# midimixer-channel.net
KiCad netlist of a schematic drawn in EAGLE
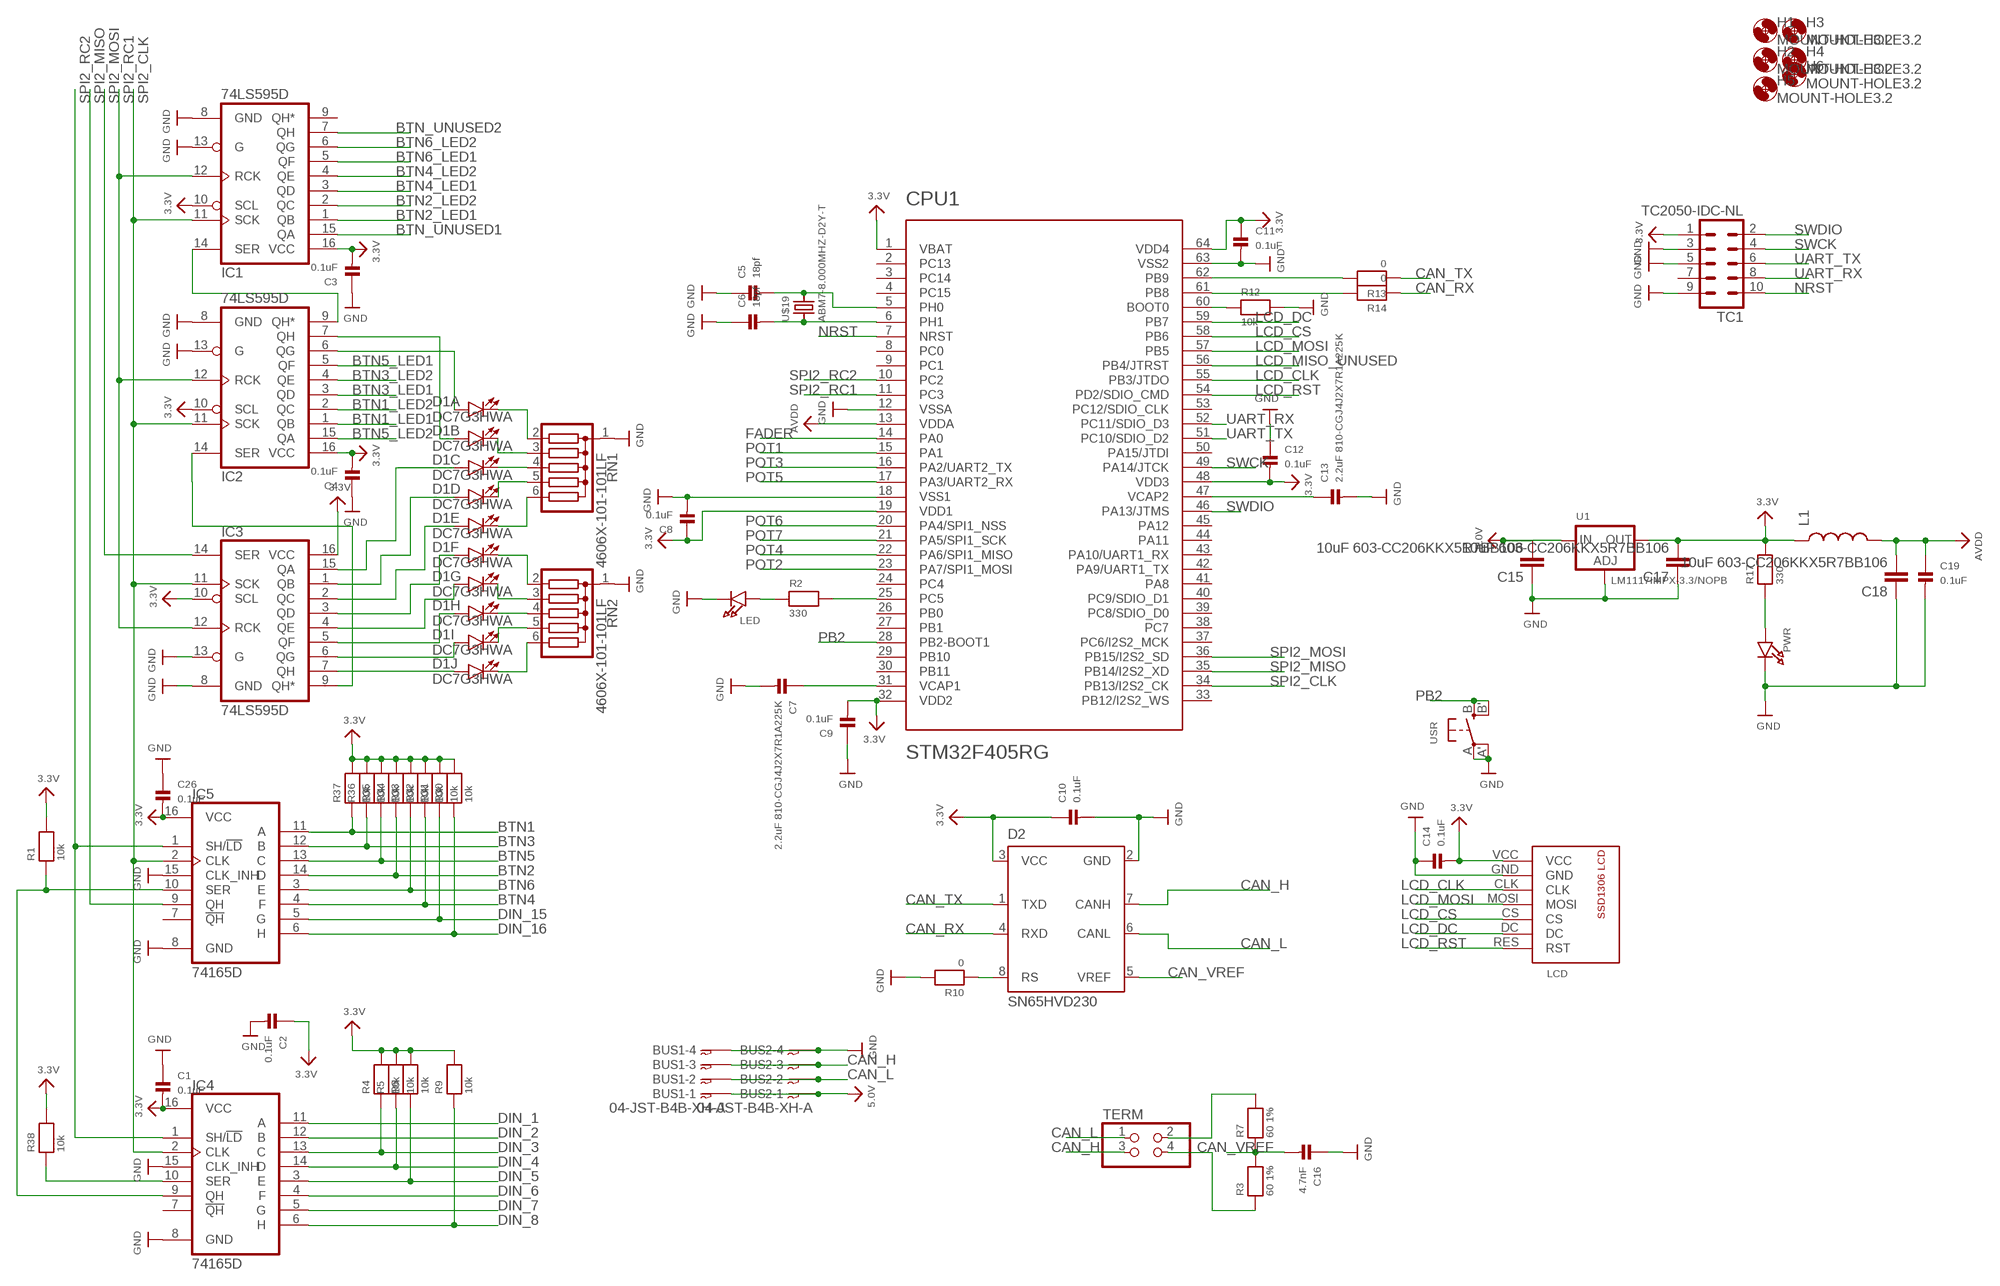
[diagram p0: schematic, sheet 1]
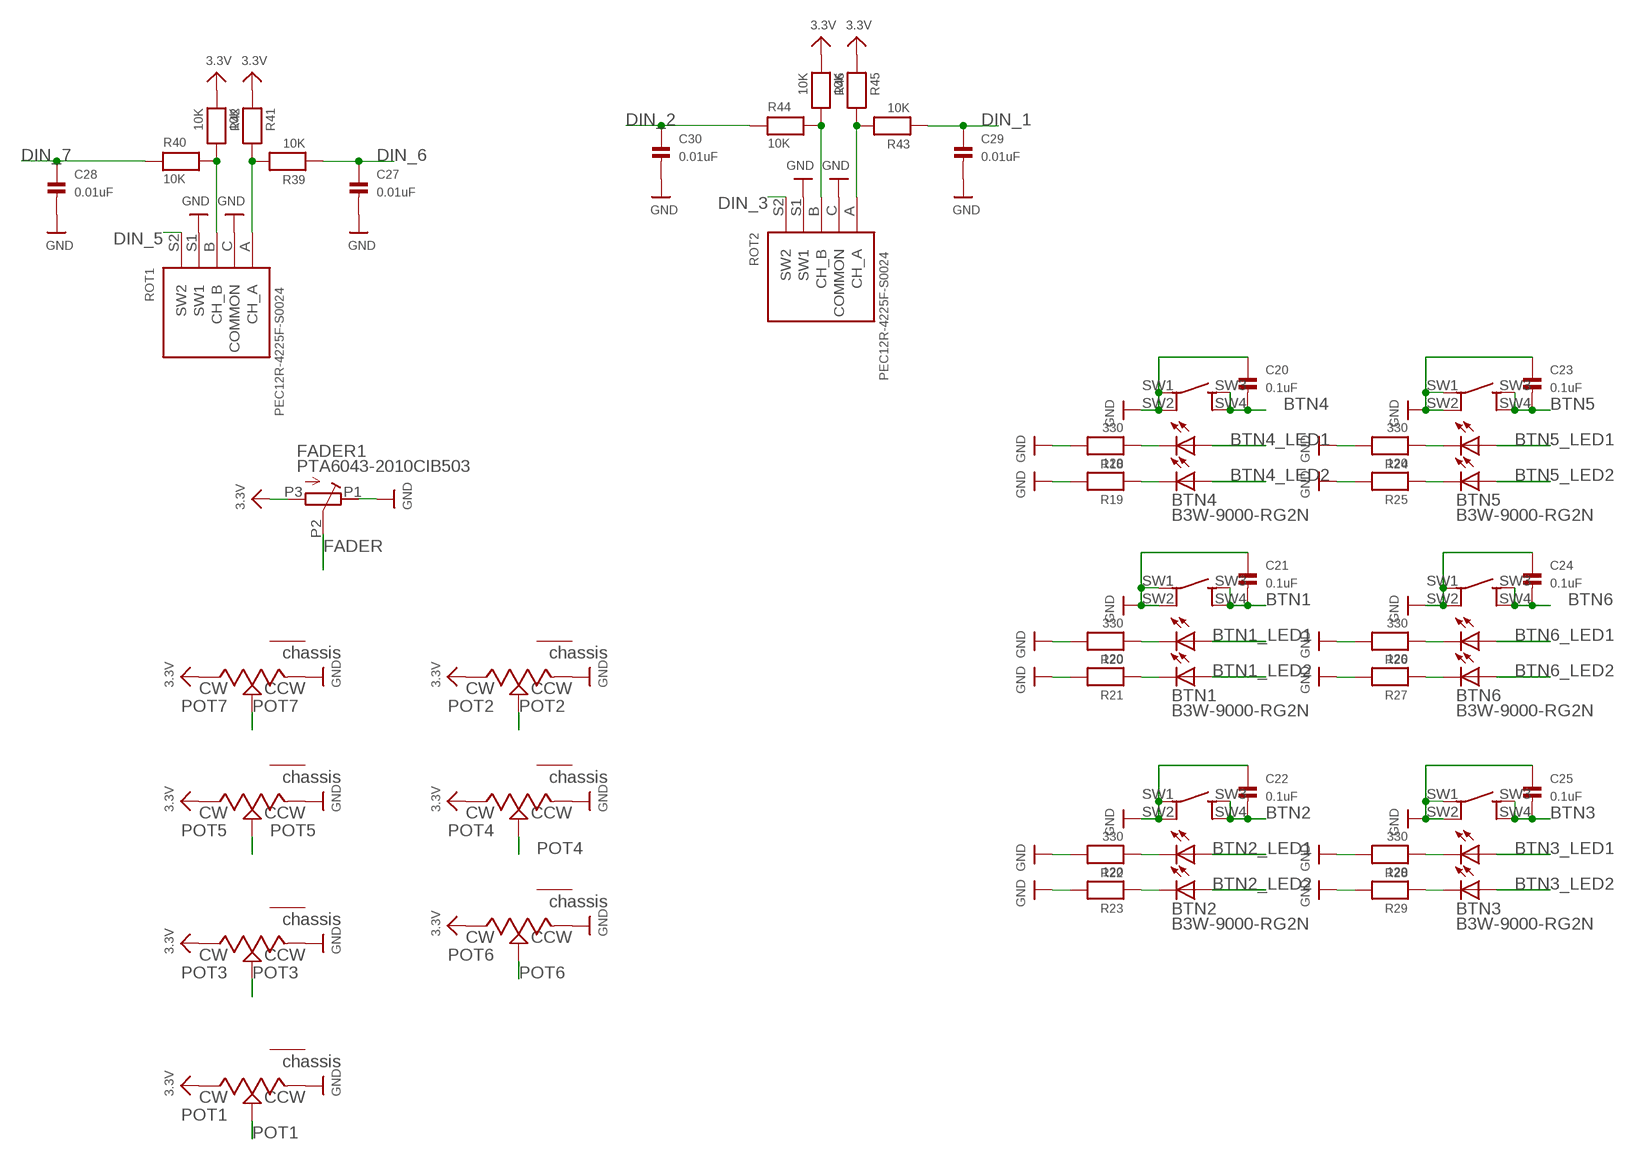
[diagram p1: schematic, sheet 2]

(export (version "E")
  (design (tool "Eeschema 10.0.6"))
  (components
    (comp (ref "BTN1")
      (value "B3W-9000-RG2N")
      (footprint "eagle-import:B3W-9000-X2X")
      (libsource (lib "eagle-import") (part "B3W-9000-RG2N"))
    )
    (comp (ref "BTN2")
      (value "B3W-9000-RG2N")
      (footprint "eagle-import:B3W-9000-X2X")
      (libsource (lib "eagle-import") (part "B3W-9000-RG2N"))
    )
    (comp (ref "BTN3")
      (value "B3W-9000-RG2N")
      (footprint "eagle-import:B3W-9000-X2X")
      (libsource (lib "eagle-import") (part "B3W-9000-RG2N"))
    )
    (comp (ref "BTN4")
      (value "B3W-9000-RG2N")
      (footprint "eagle-import:B3W-9000-X2X")
      (libsource (lib "eagle-import") (part "B3W-9000-RG2N"))
    )
    (comp (ref "BTN5")
      (value "B3W-9000-RG2N")
      (footprint "eagle-import:B3W-9000-X2X")
      (libsource (lib "eagle-import") (part "B3W-9000-RG2N"))
    )
    (comp (ref "BTN6")
      (value "B3W-9000-RG2N")
      (footprint "eagle-import:B3W-9000-X2X")
      (libsource (lib "eagle-import") (part "B3W-9000-RG2N"))
    )
    (comp (ref "C20")
      (value "0.1uF")
      (footprint "eagle-import:0603")
      (libsource (lib "eagle-import") (part "CAP_CERAMIC0603"))
    )
    (comp (ref "C21")
      (value "0.1uF")
      (footprint "eagle-import:0603")
      (libsource (lib "eagle-import") (part "CAP_CERAMIC0603"))
    )
    (comp (ref "C22")
      (value "0.1uF")
      (footprint "eagle-import:0603")
      (libsource (lib "eagle-import") (part "CAP_CERAMIC0603"))
    )
    (comp (ref "C23")
      (value "0.1uF")
      (footprint "eagle-import:0603")
      (libsource (lib "eagle-import") (part "CAP_CERAMIC0603"))
    )
    (comp (ref "C24")
      (value "0.1uF")
      (footprint "eagle-import:0603")
      (libsource (lib "eagle-import") (part "CAP_CERAMIC0603"))
    )
    (comp (ref "C25")
      (value "0.1uF")
      (footprint "eagle-import:0603")
      (libsource (lib "eagle-import") (part "CAP_CERAMIC0603"))
    )
    (comp (ref "C27")
      (value "0.01uF")
      (footprint "eagle-import:0603")
      (libsource (lib "eagle-import") (part "CAP_CERAMIC0603"))
    )
    (comp (ref "C28")
      (value "0.01uF")
      (footprint "eagle-import:0603")
      (libsource (lib "eagle-import") (part "CAP_CERAMIC0603"))
    )
    (comp (ref "C29")
      (value "0.01uF")
      (footprint "eagle-import:0603")
      (libsource (lib "eagle-import") (part "CAP_CERAMIC0603"))
    )
    (comp (ref "C30")
      (value "0.01uF")
      (footprint "eagle-import:0603")
      (libsource (lib "eagle-import") (part "CAP_CERAMIC0603"))
    )
    (comp (ref "FADER1")
      (value "PTA6043-2010CIB503")
      (footprint "eagle-import:PTA6043-2015CPB103")
      (libsource (lib "eagle-import") (part "PTA6043-2015CPB103"))
    )
    (comp (ref "POT1")
      (value "POTENTIOMETERPTV09A_VERTICAL")
      (footprint "eagle-import:PTV09A-4")
      (libsource (lib "eagle-import") (part "POTENTIOMETERPTV09A_VERTICAL"))
    )
    (comp (ref "POT2")
      (value "POTENTIOMETERPTV09A_VERTICAL")
      (footprint "eagle-import:PTV09A-4")
      (libsource (lib "eagle-import") (part "POTENTIOMETERPTV09A_VERTICAL"))
    )
    (comp (ref "POT3")
      (value "POTENTIOMETERPTV09A_VERTICAL")
      (footprint "eagle-import:PTV09A-4")
      (libsource (lib "eagle-import") (part "POTENTIOMETERPTV09A_VERTICAL"))
    )
    (comp (ref "POT4")
      (value "POTENTIOMETERPTV09A_VERTICAL")
      (footprint "eagle-import:PTV09A-4")
      (libsource (lib "eagle-import") (part "POTENTIOMETERPTV09A_VERTICAL"))
    )
    (comp (ref "POT5")
      (value "POTENTIOMETERPTV09A_VERTICAL")
      (footprint "eagle-import:PTV09A-4")
      (libsource (lib "eagle-import") (part "POTENTIOMETERPTV09A_VERTICAL"))
    )
    (comp (ref "POT6")
      (value "POTENTIOMETERPTV09A_VERTICAL")
      (footprint "eagle-import:PTV09A-4")
      (libsource (lib "eagle-import") (part "POTENTIOMETERPTV09A_VERTICAL"))
    )
    (comp (ref "POT7")
      (value "POTENTIOMETERPTV09A_VERTICAL")
      (footprint "eagle-import:PTV09A-4")
      (libsource (lib "eagle-import") (part "POTENTIOMETERPTV09A_VERTICAL"))
    )
    (comp (ref "R18")
      (value "330")
      (footprint "eagle-import:0603")
      (libsource (lib "eagle-import") (part "RESISTOR0603"))
    )
    (comp (ref "R19")
      (value "120")
      (footprint "eagle-import:0603")
      (libsource (lib "eagle-import") (part "RESISTOR0603"))
    )
    (comp (ref "R20")
      (value "330")
      (footprint "eagle-import:0603")
      (libsource (lib "eagle-import") (part "RESISTOR0603"))
    )
    (comp (ref "R21")
      (value "120")
      (footprint "eagle-import:0603")
      (libsource (lib "eagle-import") (part "RESISTOR0603"))
    )
    (comp (ref "R22")
      (value "330")
      (footprint "eagle-import:0603")
      (libsource (lib "eagle-import") (part "RESISTOR0603"))
    )
    (comp (ref "R23")
      (value "120")
      (footprint "eagle-import:0603")
      (libsource (lib "eagle-import") (part "RESISTOR0603"))
    )
    (comp (ref "R24")
      (value "330")
      (footprint "eagle-import:0603")
      (libsource (lib "eagle-import") (part "RESISTOR0603"))
    )
    (comp (ref "R25")
      (value "120")
      (footprint "eagle-import:0603")
      (libsource (lib "eagle-import") (part "RESISTOR0603"))
    )
    (comp (ref "R26")
      (value "330")
      (footprint "eagle-import:0603")
      (libsource (lib "eagle-import") (part "RESISTOR0603"))
    )
    (comp (ref "R27")
      (value "120")
      (footprint "eagle-import:0603")
      (libsource (lib "eagle-import") (part "RESISTOR0603"))
    )
    (comp (ref "R28")
      (value "330")
      (footprint "eagle-import:0603")
      (libsource (lib "eagle-import") (part "RESISTOR0603"))
    )
    (comp (ref "R29")
      (value "120")
      (footprint "eagle-import:0603")
      (libsource (lib "eagle-import") (part "RESISTOR0603"))
    )
    (comp (ref "R39")
      (value "10K")
      (footprint "eagle-import:0603")
      (libsource (lib "eagle-import") (part "RESISTOR0603"))
    )
    (comp (ref "R40")
      (value "10K")
      (footprint "eagle-import:0603")
      (libsource (lib "eagle-import") (part "RESISTOR0603"))
    )
    (comp (ref "R41")
      (value "10K")
      (footprint "eagle-import:0603")
      (libsource (lib "eagle-import") (part "RESISTOR0603"))
    )
    (comp (ref "R42")
      (value "10K")
      (footprint "eagle-import:0603")
      (libsource (lib "eagle-import") (part "RESISTOR0603"))
    )
    (comp (ref "R43")
      (value "10K")
      (footprint "eagle-import:0603")
      (libsource (lib "eagle-import") (part "RESISTOR0603"))
    )
    (comp (ref "R44")
      (value "10K")
      (footprint "eagle-import:0603")
      (libsource (lib "eagle-import") (part "RESISTOR0603"))
    )
    (comp (ref "R45")
      (value "10K")
      (footprint "eagle-import:0603")
      (libsource (lib "eagle-import") (part "RESISTOR0603"))
    )
    (comp (ref "R46")
      (value "10K")
      (footprint "eagle-import:0603")
      (libsource (lib "eagle-import") (part "RESISTOR0603"))
    )
    (comp (ref "ROT1")
      (value "PEC12R-4225F-S0024")
      (footprint "eagle-import:PEC111-4XXXK-SXXXX")
      (libsource (lib "eagle-import") (part "PEC11-4215K-S0024"))
    )
    (comp (ref "ROT2")
      (value "PEC12R-4225F-S0024")
      (footprint "eagle-import:PEC111-4XXXK-SXXXX")
      (libsource (lib "eagle-import") (part "PEC11-4215K-S0024"))
    )
    (comp (ref "BUS1")
      (value "04-JST-B4B-XH-A")
      (footprint "eagle-import:B4B-XH")
      (libsource (lib "eagle-import") (part "04-JST-B4B-XH-A"))
    )
    (comp (ref "BUS2")
      (value "04-JST-B4B-XH-A")
      (footprint "eagle-import:B4B-XH")
      (libsource (lib "eagle-import") (part "04-JST-B4B-XH-A"))
    )
    (comp (ref "C1")
      (value "0.1uF")
      (footprint "eagle-import:0603")
      (libsource (lib "eagle-import") (part "CAP_CERAMIC0603"))
    )
    (comp (ref "C2")
      (value "0.1uF")
      (footprint "eagle-import:0603")
      (libsource (lib "eagle-import") (part "CAP_CERAMIC0603"))
    )
    (comp (ref "C3")
      (value "0.1uF")
      (footprint "eagle-import:0603")
      (libsource (lib "eagle-import") (part "CAP_CERAMIC0603"))
    )
    (comp (ref "C4")
      (value "0.1uF")
      (footprint "eagle-import:0603")
      (libsource (lib "eagle-import") (part "CAP_CERAMIC0603"))
    )
    (comp (ref "C5")
      (value "18pf")
      (footprint "eagle-import:0603")
      (libsource (lib "eagle-import") (part "CAP_CERAMIC0603"))
    )
    (comp (ref "C6")
      (value "18pf")
      (footprint "eagle-import:0603")
      (libsource (lib "eagle-import") (part "CAP_CERAMIC0603"))
    )
    (comp (ref "C7")
      (value "2.2uF 810-CGJ4J2X7R1A225K")
      (footprint "eagle-import:0805")
      (libsource (lib "eagle-import") (part "CAP_CERAMIC0805"))
    )
    (comp (ref "C8")
      (value "0.1uF")
      (footprint "eagle-import:0603")
      (libsource (lib "eagle-import") (part "CAP_CERAMIC0603"))
    )
    (comp (ref "C9")
      (value "0.1uF")
      (footprint "eagle-import:0603")
      (libsource (lib "eagle-import") (part "CAP_CERAMIC0603"))
    )
    (comp (ref "C10")
      (value "0.1uF")
      (footprint "eagle-import:0603")
      (libsource (lib "eagle-import") (part "CAP_CERAMIC0603"))
    )
    (comp (ref "C11")
      (value "0.1uF")
      (footprint "eagle-import:0603")
      (libsource (lib "eagle-import") (part "CAP_CERAMIC0603"))
    )
    (comp (ref "C12")
      (value "0.1uF")
      (footprint "eagle-import:0603")
      (libsource (lib "eagle-import") (part "CAP_CERAMIC0603"))
    )
    (comp (ref "C13")
      (value "2.2uF 810-CGJ4J2X7R1A225K")
      (footprint "eagle-import:0805")
      (libsource (lib "eagle-import") (part "CAP_CERAMIC0805"))
    )
    (comp (ref "C14")
      (value "0.1uF")
      (footprint "eagle-import:0603")
      (libsource (lib "eagle-import") (part "CAP_CERAMIC0603"))
    )
    (comp (ref "C15")
      (value "10uF 603-CC206KKX5R7BB106")
      (footprint "eagle-import:1206")
      (libsource (lib "eagle-import") (part "CAP1206"))
    )
    (comp (ref "C16")
      (value "4.7nF")
      (footprint "eagle-import:0603")
      (libsource (lib "eagle-import") (part "CAP_CERAMIC0603"))
    )
    (comp (ref "C17")
      (value "10uF 603-CC206KKX5R7BB106")
      (footprint "eagle-import:1206")
      (libsource (lib "eagle-import") (part "CAP1206"))
    )
    (comp (ref "C18")
      (value "10uF 603-CC206KKX5R7BB106")
      (footprint "eagle-import:1206")
      (libsource (lib "eagle-import") (part "CAP1206"))
    )
    (comp (ref "C19")
      (value "0.1uF")
      (footprint "eagle-import:0603")
      (libsource (lib "eagle-import") (part "CAP_CERAMIC0603"))
    )
    (comp (ref "C26")
      (value "0.1uF")
      (footprint "eagle-import:0603")
      (libsource (lib "eagle-import") (part "CAP_CERAMIC0603"))
    )
    (comp (ref "CPU1")
      (value "STM32F405RG")
      (footprint "eagle-import:TQFP64")
      (libsource (lib "eagle-import") (part "STM32F405RG"))
    )
    (comp (ref "D1")
      (value "DC7G3HWA")
      (footprint "eagle-import:LED_BARGAPH_10")
      (libsource (lib "eagle-import") (part "LED_BARGRAPH_10"))
    )
    (comp (ref "D2")
      (value "SN65HVD230")
      (footprint "eagle-import:SO8")
      (libsource (lib "eagle-import") (part "SN65HVD230"))
    )
    (comp (ref "H1")
      (value "MOUNT-HOLE3.2")
      (footprint "eagle-import:3,2")
      (libsource (lib "eagle-import") (part "MOUNT-HOLE3.2"))
    )
    (comp (ref "H2")
      (value "MOUNT-HOLE3.2")
      (footprint "eagle-import:3,2")
      (libsource (lib "eagle-import") (part "MOUNT-HOLE3.2"))
    )
    (comp (ref "H3")
      (value "MOUNT-HOLE3.2")
      (footprint "eagle-import:3,2")
      (libsource (lib "eagle-import") (part "MOUNT-HOLE3.2"))
    )
    (comp (ref "H4")
      (value "MOUNT-HOLE3.2")
      (footprint "eagle-import:3,2")
      (libsource (lib "eagle-import") (part "MOUNT-HOLE3.2"))
    )
    (comp (ref "H5")
      (value "MOUNT-HOLE3.2")
      (footprint "eagle-import:3,2")
      (libsource (lib "eagle-import") (part "MOUNT-HOLE3.2"))
    )
    (comp (ref "H6")
      (value "MOUNT-HOLE3.2")
      (footprint "eagle-import:3,2")
      (libsource (lib "eagle-import") (part "MOUNT-HOLE3.2"))
    )
    (comp (ref "IC1")
      (value "74LS595D")
      (footprint "eagle-import:SO16")
      (libsource (lib "eagle-import") (part "74595DLS"))
    )
    (comp (ref "IC2")
      (value "74LS595D")
      (footprint "eagle-import:SO16")
      (libsource (lib "eagle-import") (part "74595DLS"))
    )
    (comp (ref "IC3")
      (value "74LS595D")
      (footprint "eagle-import:SO16")
      (libsource (lib "eagle-import") (part "74595DLS"))
    )
    (comp (ref "IC4")
      (value "74165D")
      (footprint "eagle-import:SO16")
      (libsource (lib "eagle-import") (part "74165D"))
    )
    (comp (ref "IC5")
      (value "74165D")
      (footprint "eagle-import:SO16")
      (libsource (lib "eagle-import") (part "74165D"))
    )
    (comp (ref "L1")
      (value "INDUCTOR0805")
      (footprint "eagle-import:0805")
      (libsource (lib "eagle-import") (part "INDUCTOR0805"))
    )
    (comp (ref "LCD")
      (value "SSD1306-7PINWITHOUT-HOLES")
      (footprint "eagle-import:SSD1306-7PIN-NO-HOLES")
      (libsource (lib "eagle-import") (part "SSD1306-7PINWITHOUT-HOLES"))
    )
    (comp (ref "LED")
      (value "LED0603")
      (footprint "eagle-import:CHIPLED_0603")
      (libsource (lib "eagle-import") (part "LED0603"))
    )
    (comp (ref "PWR")
      (value "LED0603")
      (footprint "eagle-import:CHIPLED_0603")
      (libsource (lib "eagle-import") (part "LED0603"))
    )
    (comp (ref "R1")
      (value "10k")
      (footprint "eagle-import:_0603")
      (libsource (lib "eagle-import") (part "RESISTOR_0603"))
    )
    (comp (ref "R2")
      (value "330")
      (footprint "eagle-import:0603")
      (libsource (lib "eagle-import") (part "RESISTOR0603"))
    )
    (comp (ref "R3")
      (value "60 1%")
      (footprint "eagle-import:0603")
      (libsource (lib "eagle-import") (part "RESISTOR0603"))
    )
    (comp (ref "R4")
      (value "10k")
      (footprint "eagle-import:_0603")
      (libsource (lib "eagle-import") (part "RESISTOR_0603"))
    )
    (comp (ref "R5")
      (value "10k")
      (footprint "eagle-import:_0603")
      (libsource (lib "eagle-import") (part "RESISTOR_0603"))
    )
    (comp (ref "R6")
      (value "10k")
      (footprint "eagle-import:_0603")
      (libsource (lib "eagle-import") (part "RESISTOR_0603"))
    )
    (comp (ref "R7")
      (value "60 1%")
      (footprint "eagle-import:0603")
      (libsource (lib "eagle-import") (part "RESISTOR0603"))
    )
    (comp (ref "R9")
      (value "10k")
      (footprint "eagle-import:_0603")
      (libsource (lib "eagle-import") (part "RESISTOR_0603"))
    )
    (comp (ref "R10")
      (value "0")
      (footprint "eagle-import:_0603")
      (libsource (lib "eagle-import") (part "RESISTOR_0603"))
    )
    (comp (ref "R12")
      (value "10k")
      (footprint "eagle-import:_0603")
      (libsource (lib "eagle-import") (part "RESISTOR_0603"))
    )
    (comp (ref "R13")
      (value "0")
      (footprint "eagle-import:_0603")
      (libsource (lib "eagle-import") (part "RESISTOR_0603"))
    )
    (comp (ref "R14")
      (value "0")
      (footprint "eagle-import:_0603")
      (libsource (lib "eagle-import") (part "RESISTOR_0603"))
    )
    (comp (ref "R17")
      (value "330")
      (footprint "eagle-import:0603")
      (libsource (lib "eagle-import") (part "RESISTOR0603"))
    )
    (comp (ref "R30")
      (value "10k")
      (footprint "eagle-import:_0603")
      (libsource (lib "eagle-import") (part "RESISTOR_0603"))
    )
    (comp (ref "R31")
      (value "10k")
      (footprint "eagle-import:_0603")
      (libsource (lib "eagle-import") (part "RESISTOR_0603"))
    )
    (comp (ref "R32")
      (value "10k")
      (footprint "eagle-import:_0603")
      (libsource (lib "eagle-import") (part "RESISTOR_0603"))
    )
    (comp (ref "R33")
      (value "10k")
      (footprint "eagle-import:_0603")
      (libsource (lib "eagle-import") (part "RESISTOR_0603"))
    )
    (comp (ref "R34")
      (value "10k")
      (footprint "eagle-import:_0603")
      (libsource (lib "eagle-import") (part "RESISTOR_0603"))
    )
    (comp (ref "R35")
      (value "10k")
      (footprint "eagle-import:_0603")
      (libsource (lib "eagle-import") (part "RESISTOR_0603"))
    )
    (comp (ref "R36")
      (value "10k")
      (footprint "eagle-import:_0603")
      (libsource (lib "eagle-import") (part "RESISTOR_0603"))
    )
    (comp (ref "R37")
      (value "10k")
      (footprint "eagle-import:_0603")
      (libsource (lib "eagle-import") (part "RESISTOR_0603"))
    )
    (comp (ref "R38")
      (value "10k")
      (footprint "eagle-import:_0603")
      (libsource (lib "eagle-import") (part "RESISTOR_0603"))
    )
    (comp (ref "RN1")
      (value "4606X-101-101LF")
      (footprint "eagle-import:SIL6")
      (libsource (lib "eagle-import") (part "G05R"))
    )
    (comp (ref "RN2")
      (value "4606X-101-101LF")
      (footprint "eagle-import:SIL6")
      (libsource (lib "eagle-import") (part "G05R"))
    )
    (comp (ref "TC1")
      (value "TC2050-IDC-NL")
      (footprint "eagle-import:TC2050-IDC-NL")
      (libsource (lib "eagle-import") (part "TC2050-IDC-NL"))
    )
    (comp (ref "TERM")
      (value "PINHD-2X2")
      (footprint "eagle-import:2X02")
      (libsource (lib "eagle-import") (part "PINHD-2X2"))
    )
    (comp (ref "U$19")
      (value "ABM7-8.000MHZ-D2Y-T")
      (footprint "eagle-import:ABM7-8.000MHZ-D2Y-T")
      (libsource (lib "eagle-import") (part "ABM7-8.000MHZ-D2Y-T"))
    )
    (comp (ref "U1")
      (value "LM1117IMPX-3.3/NOPB")
      (footprint "eagle-import:SOT223-R")
      (libsource (lib "eagle-import") (part "LM1117SOT223-REFLOW"))
    )
    (comp (ref "USR")
      (value "SWITCH_TACT_SMT")
      (footprint "eagle-import:EVQ-Q2")
      (libsource (lib "eagle-import") (part "SWITCH_TACT_SMT"))
    )
  )
  (nets
    (net (code "1") (name "3.3V") (class "Default")
      (node (ref "C1") (pin "2") (pinfunction "P$2_2") (pintype "passive"))
      (node (ref "C10") (pin "1") (pinfunction "P$1_1") (pintype "passive"))
      (node (ref "C11") (pin "1") (pinfunction "P$1_1") (pintype "passive"))
      (node (ref "C12") (pin "2") (pinfunction "P$2_2") (pintype "passive"))
      (node (ref "C14") (pin "2") (pinfunction "P$2_2") (pintype "passive"))
      (node (ref "C17") (pin "2") (pinfunction "2_2") (pintype "passive"))
      (node (ref "C2") (pin "1") (pinfunction "P$1_1") (pintype "passive"))
      (node (ref "C26") (pin "2") (pinfunction "P$2_2") (pintype "passive"))
      (node (ref "C3") (pin "2") (pinfunction "P$2_2") (pintype "passive"))
      (node (ref "C4") (pin "2") (pinfunction "P$2_2") (pintype "passive"))
      (node (ref "C8") (pin "1") (pinfunction "P$1_1") (pintype "passive"))
      (node (ref "C9") (pin "2") (pinfunction "P$2_2") (pintype "passive"))
      (node (ref "CPU1") (pin "1") (pinfunction "VBAT_1") (pintype "bidirectional"))
      (node (ref "CPU1") (pin "19") (pinfunction "VDD1_19") (pintype "bidirectional"))
      (node (ref "CPU1") (pin "32") (pinfunction "VDD2_32") (pintype "bidirectional"))
      (node (ref "CPU1") (pin "48") (pinfunction "VDD3_48") (pintype "bidirectional"))
      (node (ref "CPU1") (pin "64") (pinfunction "VDD4_64") (pintype "bidirectional"))
      (node (ref "D2") (pin "3") (pinfunction "VCC_3") (pintype "power_in"))
      (node (ref "FADER1") (pin "P3") (pinfunction "E_P3") (pintype "passive"))
      (node (ref "IC1") (pin "10") (pinfunction "SCL_10") (pintype "input"))
      (node (ref "IC1") (pin "16") (pinfunction "VCC_16") (pintype "power_in"))
      (node (ref "IC2") (pin "10") (pinfunction "SCL_10") (pintype "input"))
      (node (ref "IC2") (pin "16") (pinfunction "VCC_16") (pintype "power_in"))
      (node (ref "IC3") (pin "10") (pinfunction "SCL_10") (pintype "input"))
      (node (ref "IC3") (pin "16") (pinfunction "VCC_16") (pintype "power_in"))
      (node (ref "IC4") (pin "16") (pinfunction "VCC_16") (pintype "power_in"))
      (node (ref "IC5") (pin "16") (pinfunction "VCC_16") (pintype "power_in"))
      (node (ref "L1") (pin "1") (pinfunction "1_1") (pintype "passive"))
      (node (ref "LCD") (pin "VCC") (pinfunction "VCC_VCC") (pintype "bidirectional"))
      (node (ref "POT1") (pin "CW") (pinfunction "CW_CW") (pintype "passive"))
      (node (ref "POT2") (pin "CW") (pinfunction "CW_CW") (pintype "passive"))
      (node (ref "POT3") (pin "CW") (pinfunction "CW_CW") (pintype "passive"))
      (node (ref "POT4") (pin "CW") (pinfunction "CW_CW") (pintype "passive"))
      (node (ref "POT5") (pin "CW") (pinfunction "CW_CW") (pintype "passive"))
      (node (ref "POT6") (pin "CW") (pinfunction "CW_CW") (pintype "passive"))
      (node (ref "POT7") (pin "CW") (pinfunction "CW_CW") (pintype "passive"))
      (node (ref "R1") (pin "2") (pinfunction "2_2") (pintype "passive"))
      (node (ref "R17") (pin "2") (pinfunction "2_2") (pintype "passive"))
      (node (ref "R30") (pin "2") (pinfunction "2_2") (pintype "passive"))
      (node (ref "R31") (pin "2") (pinfunction "2_2") (pintype "passive"))
      (node (ref "R32") (pin "2") (pinfunction "2_2") (pintype "passive"))
      (node (ref "R33") (pin "2") (pinfunction "2_2") (pintype "passive"))
      (node (ref "R34") (pin "2") (pinfunction "2_2") (pintype "passive"))
      (node (ref "R35") (pin "2") (pinfunction "2_2") (pintype "passive"))
      (node (ref "R36") (pin "2") (pinfunction "2_2") (pintype "passive"))
      (node (ref "R37") (pin "2") (pinfunction "2_2") (pintype "passive"))
      (node (ref "R38") (pin "2") (pinfunction "2_2") (pintype "passive"))
      (node (ref "R4") (pin "2") (pinfunction "2_2") (pintype "passive"))
      (node (ref "R41") (pin "1") (pinfunction "1_1") (pintype "passive"))
      (node (ref "R42") (pin "1") (pinfunction "1_1") (pintype "passive"))
      (node (ref "R45") (pin "1") (pinfunction "1_1") (pintype "passive"))
      (node (ref "R46") (pin "1") (pinfunction "1_1") (pintype "passive"))
      (node (ref "R5") (pin "2") (pinfunction "2_2") (pintype "passive"))
      (node (ref "R6") (pin "2") (pinfunction "2_2") (pintype "passive"))
      (node (ref "R9") (pin "2") (pinfunction "2_2") (pintype "passive"))
      (node (ref "TC1") (pin "1") (pinfunction "1_1") (pintype "passive"))
      (node (ref "U1") (pin "2") (pinfunction "OUT_2") (pintype "passive"))
    )
    (net (code "2") (name "5.0V") (class "Default")
      (node (ref "BUS1") (pin "P$1") (pinfunction "1_P$1") (pintype "passive"))
      (node (ref "BUS2") (pin "P$1") (pinfunction "1_P$1") (pintype "passive"))
      (node (ref "C15") (pin "2") (pinfunction "2_2") (pintype "passive"))
      (node (ref "U1") (pin "3") (pinfunction "IN_3") (pintype "input"))
    )
    (net (code "3") (name "AVDD") (class "Default")
      (node (ref "C18") (pin "2") (pinfunction "2_2") (pintype "passive"))
      (node (ref "C19") (pin "1") (pinfunction "P$1_1") (pintype "passive"))
      (node (ref "CPU1") (pin "13") (pinfunction "VDDA_13") (pintype "bidirectional"))
      (node (ref "L1") (pin "2") (pinfunction "2_2") (pintype "passive"))
    )
    (net (code "4") (name "BTN1") (class "Default")
      (node (ref "BTN1") (pin "SW3") (pinfunction "SW2_A_SW3") (pintype "passive"))
      (node (ref "BTN1") (pin "SW4") (pinfunction "SW2_B_SW4") (pintype "passive"))
      (node (ref "C21") (pin "2") (pinfunction "P$2_2") (pintype "passive"))
      (node (ref "IC5") (pin "11") (pinfunction "A_11") (pintype "tri_state"))
      (node (ref "R37") (pin "1") (pinfunction "1_1") (pintype "passive"))
    )
    (net (code "5") (name "BTN1_LED1") (class "Default")
      (node (ref "BTN1") (pin "LED1+") (pinfunction "LED1+_LED1+") (pintype "passive"))
      (node (ref "IC2") (pin "1") (pinfunction "QB_1") (pintype "tri_state"))
    )
    (net (code "6") (name "BTN1_LED2") (class "Default")
      (node (ref "BTN1") (pin "LED2+") (pinfunction "LED2+_LED2+") (pintype "passive"))
      (node (ref "IC2") (pin "2") (pinfunction "QC_2") (pintype "tri_state"))
    )
    (net (code "7") (name "BTN2") (class "Default")
      (node (ref "BTN2") (pin "SW3") (pinfunction "SW2_A_SW3") (pintype "passive"))
      (node (ref "BTN2") (pin "SW4") (pinfunction "SW2_B_SW4") (pintype "passive"))
      (node (ref "C22") (pin "2") (pinfunction "P$2_2") (pintype "passive"))
      (node (ref "IC5") (pin "14") (pinfunction "D_14") (pintype "tri_state"))
      (node (ref "R34") (pin "1") (pinfunction "1_1") (pintype "passive"))
    )
    (net (code "8") (name "BTN2_LED1") (class "Default")
      (node (ref "BTN2") (pin "LED1+") (pinfunction "LED1+_LED1+") (pintype "passive"))
      (node (ref "IC1") (pin "1") (pinfunction "QB_1") (pintype "tri_state"))
    )
    (net (code "9") (name "BTN2_LED2") (class "Default")
      (node (ref "BTN2") (pin "LED2+") (pinfunction "LED2+_LED2+") (pintype "passive"))
      (node (ref "IC1") (pin "2") (pinfunction "QC_2") (pintype "tri_state"))
    )
    (net (code "10") (name "BTN3") (class "Default")
      (node (ref "BTN3") (pin "SW3") (pinfunction "SW2_A_SW3") (pintype "passive"))
      (node (ref "BTN3") (pin "SW4") (pinfunction "SW2_B_SW4") (pintype "passive"))
      (node (ref "C25") (pin "2") (pinfunction "P$2_2") (pintype "passive"))
      (node (ref "IC5") (pin "12") (pinfunction "B_12") (pintype "tri_state"))
      (node (ref "R36") (pin "1") (pinfunction "1_1") (pintype "passive"))
    )
    (net (code "11") (name "BTN3_LED1") (class "Default")
      (node (ref "BTN3") (pin "LED1+") (pinfunction "LED1+_LED1+") (pintype "passive"))
      (node (ref "IC2") (pin "3") (pinfunction "QD_3") (pintype "tri_state"))
    )
    (net (code "12") (name "BTN3_LED2") (class "Default")
      (node (ref "BTN3") (pin "LED2+") (pinfunction "LED2+_LED2+") (pintype "passive"))
      (node (ref "IC2") (pin "4") (pinfunction "QE_4") (pintype "tri_state"))
    )
    (net (code "13") (name "BTN4") (class "Default")
      (node (ref "BTN4") (pin "SW3") (pinfunction "SW2_A_SW3") (pintype "passive"))
      (node (ref "BTN4") (pin "SW4") (pinfunction "SW2_B_SW4") (pintype "passive"))
      (node (ref "C20") (pin "2") (pinfunction "P$2_2") (pintype "passive"))
      (node (ref "IC5") (pin "4") (pinfunction "F_4") (pintype "tri_state"))
      (node (ref "R32") (pin "1") (pinfunction "1_1") (pintype "passive"))
    )
    (net (code "14") (name "BTN4_LED1") (class "Default")
      (node (ref "BTN4") (pin "LED1+") (pinfunction "LED1+_LED1+") (pintype "passive"))
      (node (ref "IC1") (pin "3") (pinfunction "QD_3") (pintype "tri_state"))
    )
    (net (code "15") (name "BTN4_LED2") (class "Default")
      (node (ref "BTN4") (pin "LED2+") (pinfunction "LED2+_LED2+") (pintype "passive"))
      (node (ref "IC1") (pin "4") (pinfunction "QE_4") (pintype "tri_state"))
    )
    (net (code "16") (name "BTN5") (class "Default")
      (node (ref "BTN5") (pin "SW3") (pinfunction "SW2_A_SW3") (pintype "passive"))
      (node (ref "BTN5") (pin "SW4") (pinfunction "SW2_B_SW4") (pintype "passive"))
      (node (ref "C23") (pin "2") (pinfunction "P$2_2") (pintype "passive"))
      (node (ref "IC5") (pin "13") (pinfunction "C_13") (pintype "tri_state"))
      (node (ref "R35") (pin "1") (pinfunction "1_1") (pintype "passive"))
    )
    (net (code "17") (name "BTN5_LED1") (class "Default")
      (node (ref "BTN5") (pin "LED1+") (pinfunction "LED1+_LED1+") (pintype "passive"))
      (node (ref "IC2") (pin "5") (pinfunction "QF_5") (pintype "tri_state"))
    )
    (net (code "18") (name "BTN5_LED2") (class "Default")
      (node (ref "BTN5") (pin "LED2+") (pinfunction "LED2+_LED2+") (pintype "passive"))
      (node (ref "IC2") (pin "15") (pinfunction "QA_15") (pintype "tri_state"))
    )
    (net (code "19") (name "BTN6") (class "Default")
      (node (ref "BTN6") (pin "SW3") (pinfunction "SW2_A_SW3") (pintype "passive"))
      (node (ref "BTN6") (pin "SW4") (pinfunction "SW2_B_SW4") (pintype "passive"))
      (node (ref "C24") (pin "2") (pinfunction "P$2_2") (pintype "passive"))
      (node (ref "IC5") (pin "3") (pinfunction "E_3") (pintype "tri_state"))
      (node (ref "R33") (pin "1") (pinfunction "1_1") (pintype "passive"))
    )
    (net (code "20") (name "BTN6_LED1") (class "Default")
      (node (ref "BTN6") (pin "LED1+") (pinfunction "LED1+_LED1+") (pintype "passive"))
      (node (ref "IC1") (pin "5") (pinfunction "QF_5") (pintype "tri_state"))
    )
    (net (code "21") (name "BTN6_LED2") (class "Default")
      (node (ref "BTN6") (pin "LED2+") (pinfunction "LED2+_LED2+") (pintype "passive"))
      (node (ref "IC1") (pin "6") (pinfunction "QG_6") (pintype "tri_state"))
    )
    (net (code "22") (name "BTN_UNUSED1") (class "Default")
      (node (ref "IC1") (pin "15") (pinfunction "QA_15") (pintype "tri_state"))
    )
    (net (code "23") (name "BTN_UNUSED2") (class "Default")
      (node (ref "IC1") (pin "7") (pinfunction "QH_7") (pintype "tri_state"))
    )
    (net (code "24") (name "CAN_H") (class "Default")
      (node (ref "BUS1") (pin "P$3") (pinfunction "1_P$3") (pintype "passive"))
      (node (ref "BUS2") (pin "P$3") (pinfunction "1_P$3") (pintype "passive"))
      (node (ref "D2") (pin "7") (pinfunction "CANH_7") (pintype "bidirectional"))
      (node (ref "TERM") (pin "3") (pinfunction "3_3") (pintype "passive"))
    )
    (net (code "25") (name "CAN_L") (class "Default")
      (node (ref "BUS1") (pin "P$2") (pinfunction "1_P$2") (pintype "passive"))
      (node (ref "BUS2") (pin "P$2") (pinfunction "1_P$2") (pintype "passive"))
      (node (ref "D2") (pin "6") (pinfunction "CANL_6") (pintype "bidirectional"))
      (node (ref "TERM") (pin "1") (pinfunction "1_1") (pintype "passive"))
    )
    (net (code "26") (name "CAN_RX") (class "Default")
      (node (ref "D2") (pin "4") (pinfunction "RXD_4") (pintype "output"))
      (node (ref "R14") (pin "1") (pinfunction "1_1") (pintype "passive"))
    )
    (net (code "27") (name "CAN_TX") (class "Default")
      (node (ref "D2") (pin "1") (pinfunction "TXD_1") (pintype "input"))
      (node (ref "R13") (pin "1") (pinfunction "1_1") (pintype "passive"))
    )
    (net (code "28") (name "CAN_VREF") (class "Default")
      (node (ref "C16") (pin "2") (pinfunction "P$2_2") (pintype "passive"))
      (node (ref "D2") (pin "5") (pinfunction "VREF_5") (pintype "output"))
      (node (ref "R3") (pin "2") (pinfunction "2_2") (pintype "passive"))
      (node (ref "R7") (pin "1") (pinfunction "1_1") (pintype "passive"))
    )
    (net (code "29") (name "DIN_1") (class "Default")
      (node (ref "C29") (pin "1") (pinfunction "P$1_1") (pintype "passive"))
      (node (ref "IC4") (pin "11") (pinfunction "A_11") (pintype "tri_state"))
      (node (ref "R43") (pin "1") (pinfunction "1_1") (pintype "passive"))
    )
    (net (code "30") (name "DIN_2") (class "Default")
      (node (ref "C30") (pin "1") (pinfunction "P$1_1") (pintype "passive"))
      (node (ref "IC4") (pin "12") (pinfunction "B_12") (pintype "tri_state"))
      (node (ref "R44") (pin "1") (pinfunction "1_1") (pintype "passive"))
    )
    (net (code "31") (name "DIN_3") (class "Default")
      (node (ref "IC4") (pin "13") (pinfunction "C_13") (pintype "tri_state"))
      (node (ref "R4") (pin "1") (pinfunction "1_1") (pintype "passive"))
      (node (ref "ROT2") (pin "S2") (pinfunction "SW2_S2") (pintype "bidirectional"))
    )
    (net (code "32") (name "DIN_4") (class "Default")
      (node (ref "IC4") (pin "14") (pinfunction "D_14") (pintype "tri_state"))
      (node (ref "R5") (pin "1") (pinfunction "1_1") (pintype "passive"))
    )
    (net (code "33") (name "DIN_5") (class "Default")
      (node (ref "IC4") (pin "3") (pinfunction "E_3") (pintype "tri_state"))
      (node (ref "R6") (pin "1") (pinfunction "1_1") (pintype "passive"))
      (node (ref "ROT1") (pin "S2") (pinfunction "SW2_S2") (pintype "bidirectional"))
    )
    (net (code "34") (name "DIN_6") (class "Default")
      (node (ref "C27") (pin "1") (pinfunction "P$1_1") (pintype "passive"))
      (node (ref "IC4") (pin "4") (pinfunction "F_4") (pintype "tri_state"))
      (node (ref "R39") (pin "1") (pinfunction "1_1") (pintype "passive"))
    )
    (net (code "35") (name "DIN_7") (class "Default")
      (node (ref "C28") (pin "1") (pinfunction "P$1_1") (pintype "passive"))
      (node (ref "IC4") (pin "5") (pinfunction "G_5") (pintype "tri_state"))
      (node (ref "R40") (pin "1") (pinfunction "1_1") (pintype "passive"))
    )
    (net (code "36") (name "DIN_8") (class "Default")
      (node (ref "IC4") (pin "6") (pinfunction "H_6") (pintype "tri_state"))
      (node (ref "R9") (pin "1") (pinfunction "1_1") (pintype "passive"))
    )
    (net (code "37") (name "DIN_15") (class "Default")
      (node (ref "IC5") (pin "5") (pinfunction "G_5") (pintype "tri_state"))
      (node (ref "R31") (pin "1") (pinfunction "1_1") (pintype "passive"))
    )
    (net (code "38") (name "DIN_16") (class "Default")
      (node (ref "IC5") (pin "6") (pinfunction "H_6") (pintype "tri_state"))
      (node (ref "R30") (pin "1") (pinfunction "1_1") (pintype "passive"))
    )
    (net (code "39") (name "FADER") (class "Default")
      (node (ref "CPU1") (pin "14") (pinfunction "PA0_14") (pintype "bidirectional"))
      (node (ref "FADER1") (pin "P2") (pinfunction "S_P2") (pintype "passive"))
    )
    (net (code "40") (name "GND") (class "Default")
      (node (ref "BTN1") (pin "SW1") (pinfunction "SW1_A_SW1") (pintype "passive"))
      (node (ref "BTN1") (pin "SW2") (pinfunction "SW1_B_SW2") (pintype "passive"))
      (node (ref "BTN2") (pin "SW1") (pinfunction "SW1_A_SW1") (pintype "passive"))
      (node (ref "BTN2") (pin "SW2") (pinfunction "SW1_B_SW2") (pintype "passive"))
      (node (ref "BTN3") (pin "SW1") (pinfunction "SW1_A_SW1") (pintype "passive"))
      (node (ref "BTN3") (pin "SW2") (pinfunction "SW1_B_SW2") (pintype "passive"))
      (node (ref "BTN4") (pin "SW1") (pinfunction "SW1_A_SW1") (pintype "passive"))
      (node (ref "BTN4") (pin "SW2") (pinfunction "SW1_B_SW2") (pintype "passive"))
      (node (ref "BTN5") (pin "SW1") (pinfunction "SW1_A_SW1") (pintype "passive"))
      (node (ref "BTN5") (pin "SW2") (pinfunction "SW1_B_SW2") (pintype "passive"))
      (node (ref "BTN6") (pin "SW1") (pinfunction "SW1_A_SW1") (pintype "passive"))
      (node (ref "BTN6") (pin "SW2") (pinfunction "SW1_B_SW2") (pintype "passive"))
      (node (ref "BUS1") (pin "P$4") (pinfunction "1_P$4") (pintype "passive"))
      (node (ref "BUS2") (pin "P$4") (pinfunction "1_P$4") (pintype "passive"))
      (node (ref "C1") (pin "1") (pinfunction "P$1_1") (pintype "passive"))
      (node (ref "C10") (pin "2") (pinfunction "P$2_2") (pintype "passive"))
      (node (ref "C11") (pin "2") (pinfunction "P$2_2") (pintype "passive"))
      (node (ref "C12") (pin "1") (pinfunction "P$1_1") (pintype "passive"))
      (node (ref "C13") (pin "2") (pinfunction "P$2_2") (pintype "passive"))
      (node (ref "C14") (pin "1") (pinfunction "P$1_1") (pintype "passive"))
      (node (ref "C15") (pin "1") (pinfunction "1_1") (pintype "passive"))
      (node (ref "C16") (pin "1") (pinfunction "P$1_1") (pintype "passive"))
      (node (ref "C17") (pin "1") (pinfunction "1_1") (pintype "passive"))
      (node (ref "C18") (pin "1") (pinfunction "1_1") (pintype "passive"))
      (node (ref "C19") (pin "2") (pinfunction "P$2_2") (pintype "passive"))
      (node (ref "C2") (pin "2") (pinfunction "P$2_2") (pintype "passive"))
      (node (ref "C20") (pin "1") (pinfunction "P$1_1") (pintype "passive"))
      (node (ref "C21") (pin "1") (pinfunction "P$1_1") (pintype "passive"))
      (node (ref "C22") (pin "1") (pinfunction "P$1_1") (pintype "passive"))
      (node (ref "C23") (pin "1") (pinfunction "P$1_1") (pintype "passive"))
      (node (ref "C24") (pin "1") (pinfunction "P$1_1") (pintype "passive"))
      (node (ref "C25") (pin "1") (pinfunction "P$1_1") (pintype "passive"))
      (node (ref "C26") (pin "1") (pinfunction "P$1_1") (pintype "passive"))
      (node (ref "C27") (pin "2") (pinfunction "P$2_2") (pintype "passive"))
      (node (ref "C28") (pin "2") (pinfunction "P$2_2") (pintype "passive"))
      (node (ref "C29") (pin "2") (pinfunction "P$2_2") (pintype "passive"))
      (node (ref "C3") (pin "1") (pinfunction "P$1_1") (pintype "passive"))
      (node (ref "C30") (pin "2") (pinfunction "P$2_2") (pintype "passive"))
      (node (ref "C4") (pin "1") (pinfunction "P$1_1") (pintype "passive"))
      (node (ref "C5") (pin "1") (pinfunction "P$1_1") (pintype "passive"))
      (node (ref "C6") (pin "1") (pinfunction "P$1_1") (pintype "passive"))
      (node (ref "C7") (pin "2") (pinfunction "P$2_2") (pintype "passive"))
      (node (ref "C8") (pin "2") (pinfunction "P$2_2") (pintype "passive"))
      (node (ref "C9") (pin "1") (pinfunction "P$1_1") (pintype "passive"))
      (node (ref "CPU1") (pin "12") (pinfunction "VSSA_12") (pintype "bidirectional"))
      (node (ref "CPU1") (pin "18") (pinfunction "VSS1_18") (pintype "bidirectional"))
      (node (ref "CPU1") (pin "63") (pinfunction "VSS2_63") (pintype "bidirectional"))
      (node (ref "D2") (pin "2") (pinfunction "GND_2") (pintype "power_in"))
      (node (ref "FADER1") (pin "P1") (pinfunction "A_P1") (pintype "passive"))
      (node (ref "IC1") (pin "13") (pinfunction "G_13") (pintype "input"))
      (node (ref "IC1") (pin "8") (pinfunction "GND_8") (pintype "power_in"))
      (node (ref "IC2") (pin "13") (pinfunction "G_13") (pintype "input"))
      (node (ref "IC2") (pin "8") (pinfunction "GND_8") (pintype "power_in"))
      (node (ref "IC3") (pin "13") (pinfunction "G_13") (pintype "input"))
      (node (ref "IC3") (pin "8") (pinfunction "GND_8") (pintype "power_in"))
      (node (ref "IC4") (pin "15") (pinfunction "CLK_INH_15") (pintype "input"))
      (node (ref "IC4") (pin "8") (pinfunction "GND_8") (pintype "power_in"))
      (node (ref "IC5") (pin "15") (pinfunction "CLK_INH_15") (pintype "input"))
      (node (ref "IC5") (pin "8") (pinfunction "GND_8") (pintype "power_in"))
      (node (ref "LCD") (pin "GND") (pinfunction "GND_GND") (pintype "bidirectional"))
      (node (ref "LED") (pin "C") (pinfunction "C_C") (pintype "passive"))
      (node (ref "POT1") (pin "CCW") (pinfunction "CCW_CCW") (pintype "passive"))
      (node (ref "POT2") (pin "CCW") (pinfunction "CCW_CCW") (pintype "passive"))
      (node (ref "POT3") (pin "CCW") (pinfunction "CCW_CCW") (pintype "passive"))
      (node (ref "POT4") (pin "CCW") (pinfunction "CCW_CCW") (pintype "passive"))
      (node (ref "POT5") (pin "CCW") (pinfunction "CCW_CCW") (pintype "passive"))
      (node (ref "POT6") (pin "CCW") (pinfunction "CCW_CCW") (pintype "passive"))
      (node (ref "POT7") (pin "CCW") (pinfunction "CCW_CCW") (pintype "passive"))
      (node (ref "PWR") (pin "C") (pinfunction "C_C") (pintype "passive"))
      (node (ref "R10") (pin "2") (pinfunction "2_2") (pintype "passive"))
      (node (ref "R12") (pin "2") (pinfunction "2_2") (pintype "passive"))
      (node (ref "R18") (pin "2") (pinfunction "2_2") (pintype "passive"))
      (node (ref "R19") (pin "2") (pinfunction "2_2") (pintype "passive"))
      (node (ref "R20") (pin "2") (pinfunction "2_2") (pintype "passive"))
      (node (ref "R21") (pin "2") (pinfunction "2_2") (pintype "passive"))
      (node (ref "R22") (pin "2") (pinfunction "2_2") (pintype "passive"))
      (node (ref "R23") (pin "2") (pinfunction "2_2") (pintype "passive"))
      (node (ref "R24") (pin "2") (pinfunction "2_2") (pintype "passive"))
      (node (ref "R25") (pin "2") (pinfunction "2_2") (pintype "passive"))
      (node (ref "R26") (pin "2") (pinfunction "2_2") (pintype "passive"))
      (node (ref "R27") (pin "2") (pinfunction "2_2") (pintype "passive"))
      (node (ref "R28") (pin "2") (pinfunction "2_2") (pintype "passive"))
      (node (ref "R29") (pin "2") (pinfunction "2_2") (pintype "passive"))
      (node (ref "RN1") (pin "1") (pinfunction "1_1") (pintype "passive"))
      (node (ref "RN2") (pin "1") (pinfunction "1_1") (pintype "passive"))
      (node (ref "ROT1") (pin "C") (pinfunction "COMMON_C") (pintype "input"))
      (node (ref "ROT1") (pin "S1") (pinfunction "SW1_S1") (pintype "bidirectional"))
      (node (ref "ROT2") (pin "C") (pinfunction "COMMON_C") (pintype "input"))
      (node (ref "ROT2") (pin "S1") (pinfunction "SW1_S1") (pintype "bidirectional"))
      (node (ref "TC1") (pin "3") (pinfunction "3_3") (pintype "passive"))
      (node (ref "TC1") (pin "5") (pinfunction "5_5") (pintype "passive"))
      (node (ref "TC1") (pin "9") (pinfunction "9_9") (pintype "passive"))
      (node (ref "U1") (pin "1") (pinfunction "ADJ_1") (pintype "input"))
      (node (ref "USR") (pin "A") (pinfunction "P_A") (pintype "passive"))
      (node (ref "USR") (pin "A'") (pinfunction "P1_A'") (pintype "passive"))
    )
    (net (code "41") (name "LCD_CLK") (class "Default")
      (node (ref "CPU1") (pin "55") (pinfunction "PB3/JTDO_55") (pintype "bidirectional"))
      (node (ref "LCD") (pin "CLK") (pinfunction "CLK_CLK") (pintype "bidirectional"))
    )
    (net (code "42") (name "LCD_CS") (class "Default")
      (node (ref "CPU1") (pin "58") (pinfunction "PB6_58") (pintype "bidirectional"))
      (node (ref "LCD") (pin "CS") (pinfunction "CS_CS") (pintype "bidirectional"))
    )
    (net (code "43") (name "LCD_DC") (class "Default")
      (node (ref "CPU1") (pin "59") (pinfunction "PB7_59") (pintype "bidirectional"))
      (node (ref "LCD") (pin "DC") (pinfunction "DC_DC") (pintype "bidirectional"))
    )
    (net (code "44") (name "LCD_MISO_UNUSED") (class "Default")
      (node (ref "CPU1") (pin "56") (pinfunction "PB4/JTRST_56") (pintype "bidirectional"))
    )
    (net (code "45") (name "LCD_MOSI") (class "Default")
      (node (ref "CPU1") (pin "57") (pinfunction "PB5_57") (pintype "bidirectional"))
      (node (ref "LCD") (pin "MOSI") (pinfunction "MOSI_MOSI") (pintype "bidirectional"))
    )
    (net (code "46") (name "LCD_RST") (class "Default")
      (node (ref "CPU1") (pin "54") (pinfunction "PD2/SDIO_CMD_54") (pintype "bidirectional"))
      (node (ref "LCD") (pin "RES") (pinfunction "RST_RES") (pintype "bidirectional"))
    )
    (net (code "47") (name "NRST") (class "Default")
      (node (ref "CPU1") (pin "7") (pinfunction "NRST_7") (pintype "bidirectional"))
      (node (ref "TC1") (pin "10") (pinfunction "10_10") (pintype "passive"))
    )
    (net (code "48") (name "Net-(BTN1-PadLED1-)") (class "Default")
      (node (ref "BTN1") (pin "LED1-") (pinfunction "LED1-_LED1-") (pintype "passive"))
      (node (ref "R20") (pin "1") (pinfunction "1_1") (pintype "passive"))
    )
    (net (code "49") (name "Net-(BTN1-PadLED2-)") (class "Default")
      (node (ref "BTN1") (pin "LED2-") (pinfunction "LED2-_LED2-") (pintype "passive"))
      (node (ref "R21") (pin "1") (pinfunction "1_1") (pintype "passive"))
    )
    (net (code "50") (name "Net-(BTN2-PadLED1-)") (class "Default")
      (node (ref "BTN2") (pin "LED1-") (pinfunction "LED1-_LED1-") (pintype "passive"))
      (node (ref "R22") (pin "1") (pinfunction "1_1") (pintype "passive"))
    )
    (net (code "51") (name "Net-(BTN2-PadLED2-)") (class "Default")
      (node (ref "BTN2") (pin "LED2-") (pinfunction "LED2-_LED2-") (pintype "passive"))
      (node (ref "R23") (pin "1") (pinfunction "1_1") (pintype "passive"))
    )
    (net (code "52") (name "Net-(BTN3-PadLED1-)") (class "Default")
      (node (ref "BTN3") (pin "LED1-") (pinfunction "LED1-_LED1-") (pintype "passive"))
      (node (ref "R28") (pin "1") (pinfunction "1_1") (pintype "passive"))
    )
    (net (code "53") (name "Net-(BTN3-PadLED2-)") (class "Default")
      (node (ref "BTN3") (pin "LED2-") (pinfunction "LED2-_LED2-") (pintype "passive"))
      (node (ref "R29") (pin "1") (pinfunction "1_1") (pintype "passive"))
    )
    (net (code "54") (name "Net-(BTN4-PadLED1-)") (class "Default")
      (node (ref "BTN4") (pin "LED1-") (pinfunction "LED1-_LED1-") (pintype "passive"))
      (node (ref "R18") (pin "1") (pinfunction "1_1") (pintype "passive"))
    )
    (net (code "55") (name "Net-(BTN4-PadLED2-)") (class "Default")
      (node (ref "BTN4") (pin "LED2-") (pinfunction "LED2-_LED2-") (pintype "passive"))
      (node (ref "R19") (pin "1") (pinfunction "1_1") (pintype "passive"))
    )
    (net (code "56") (name "Net-(BTN5-PadLED1-)") (class "Default")
      (node (ref "BTN5") (pin "LED1-") (pinfunction "LED1-_LED1-") (pintype "passive"))
      (node (ref "R24") (pin "1") (pinfunction "1_1") (pintype "passive"))
    )
    (net (code "57") (name "Net-(BTN5-PadLED2-)") (class "Default")
      (node (ref "BTN5") (pin "LED2-") (pinfunction "LED2-_LED2-") (pintype "passive"))
      (node (ref "R25") (pin "1") (pinfunction "1_1") (pintype "passive"))
    )
    (net (code "58") (name "Net-(BTN6-PadLED1-)") (class "Default")
      (node (ref "BTN6") (pin "LED1-") (pinfunction "LED1-_LED1-") (pintype "passive"))
      (node (ref "R26") (pin "1") (pinfunction "1_1") (pintype "passive"))
    )
    (net (code "59") (name "Net-(BTN6-PadLED2-)") (class "Default")
      (node (ref "BTN6") (pin "LED2-") (pinfunction "LED2-_LED2-") (pintype "passive"))
      (node (ref "R27") (pin "1") (pinfunction "1_1") (pintype "passive"))
    )
    (net (code "60") (name "Net-(C5-P$2)") (class "Default")
      (node (ref "C5") (pin "2") (pinfunction "P$2_2") (pintype "passive"))
      (node (ref "CPU1") (pin "5") (pinfunction "PH0_5") (pintype "bidirectional"))
      (node (ref "U$19") (pin "P$2") (pinfunction "2_P$2") (pintype "passive"))
    )
    (net (code "61") (name "Net-(C6-P$2)") (class "Default")
      (node (ref "C6") (pin "2") (pinfunction "P$2_2") (pintype "passive"))
      (node (ref "CPU1") (pin "6") (pinfunction "PH1_6") (pintype "bidirectional"))
      (node (ref "U$19") (pin "P$1") (pinfunction "1_P$1") (pintype "passive"))
    )
    (net (code "62") (name "Net-(C7-P$1)") (class "Default")
      (node (ref "C7") (pin "1") (pinfunction "P$1_1") (pintype "passive"))
      (node (ref "CPU1") (pin "31") (pinfunction "VCAP1_31") (pintype "bidirectional"))
    )
    (net (code "63") (name "Net-(C13-P$1)") (class "Default")
      (node (ref "C13") (pin "1") (pinfunction "P$1_1") (pintype "passive"))
      (node (ref "CPU1") (pin "47") (pinfunction "VCAP2_47") (pintype "bidirectional"))
    )
    (net (code "64") (name "Net-(CPU1-BOOT0)") (class "Default")
      (node (ref "CPU1") (pin "60") (pinfunction "BOOT0_60") (pintype "bidirectional"))
      (node (ref "R12") (pin "1") (pinfunction "1_1") (pintype "passive"))
    )
    (net (code "65") (name "Net-(CPU1-PB8)") (class "Default")
      (node (ref "CPU1") (pin "61") (pinfunction "PB8_61") (pintype "bidirectional"))
      (node (ref "R14") (pin "2") (pinfunction "2_2") (pintype "passive"))
    )
    (net (code "66") (name "Net-(CPU1-PB9)") (class "Default")
      (node (ref "CPU1") (pin "62") (pinfunction "PB9_62") (pintype "bidirectional"))
      (node (ref "R13") (pin "2") (pinfunction "2_2") (pintype "passive"))
    )
    (net (code "67") (name "Net-(CPU1-PC5)") (class "Default")
      (node (ref "CPU1") (pin "25") (pinfunction "PC5_25") (pintype "bidirectional"))
      (node (ref "R2") (pin "2") (pinfunction "2_2") (pintype "passive"))
    )
    (net (code "68") (name "Net-(D1A-A)") (class "Default")
      (node (ref "D1") (pin "1") (pinfunction "A_1") (pintype "passive"))
      (node (ref "IC2") (pin "6") (pinfunction "QG_6") (pintype "tri_state"))
    )
    (net (code "69") (name "Net-(D1A-C)") (class "Default")
      (node (ref "D1") (pin "20") (pinfunction "C_20") (pintype "passive"))
      (node (ref "RN1") (pin "2") (pinfunction "2_2") (pintype "passive"))
    )
    (net (code "70") (name "Net-(D1B-A)") (class "Default")
      (node (ref "D1") (pin "2") (pinfunction "A_2") (pintype "passive"))
      (node (ref "IC2") (pin "7") (pinfunction "QH_7") (pintype "tri_state"))
    )
    (net (code "71") (name "Net-(D1B-C)") (class "Default")
      (node (ref "D1") (pin "19") (pinfunction "C_19") (pintype "passive"))
      (node (ref "RN1") (pin "3") (pinfunction "3_3") (pintype "passive"))
    )
    (net (code "72") (name "Net-(D1C-A)") (class "Default")
      (node (ref "D1") (pin "3") (pinfunction "A_3") (pintype "passive"))
      (node (ref "IC3") (pin "15") (pinfunction "QA_15") (pintype "tri_state"))
    )
    (net (code "73") (name "Net-(D1C-C)") (class "Default")
      (node (ref "D1") (pin "18") (pinfunction "C_18") (pintype "passive"))
      (node (ref "RN1") (pin "4") (pinfunction "4_4") (pintype "passive"))
    )
    (net (code "74") (name "Net-(D1D-A)") (class "Default")
      (node (ref "D1") (pin "4") (pinfunction "A_4") (pintype "passive"))
      (node (ref "IC3") (pin "1") (pinfunction "QB_1") (pintype "tri_state"))
    )
    (net (code "75") (name "Net-(D1D-C)") (class "Default")
      (node (ref "D1") (pin "17") (pinfunction "C_17") (pintype "passive"))
      (node (ref "RN1") (pin "5") (pinfunction "5_5") (pintype "passive"))
    )
    (net (code "76") (name "Net-(D1E-A)") (class "Default")
      (node (ref "D1") (pin "5") (pinfunction "A_5") (pintype "passive"))
      (node (ref "IC3") (pin "2") (pinfunction "QC_2") (pintype "tri_state"))
    )
    (net (code "77") (name "Net-(D1E-C)") (class "Default")
      (node (ref "D1") (pin "16") (pinfunction "C_16") (pintype "passive"))
      (node (ref "RN1") (pin "6") (pinfunction "6_6") (pintype "passive"))
    )
    (net (code "78") (name "Net-(D1F-A)") (class "Default")
      (node (ref "D1") (pin "6") (pinfunction "A_6") (pintype "passive"))
      (node (ref "IC3") (pin "3") (pinfunction "QD_3") (pintype "tri_state"))
    )
    (net (code "79") (name "Net-(D1F-C)") (class "Default")
      (node (ref "D1") (pin "15") (pinfunction "C_15") (pintype "passive"))
      (node (ref "RN2") (pin "2") (pinfunction "2_2") (pintype "passive"))
    )
    (net (code "80") (name "Net-(D1G-A)") (class "Default")
      (node (ref "D1") (pin "7") (pinfunction "A_7") (pintype "passive"))
      (node (ref "IC3") (pin "4") (pinfunction "QE_4") (pintype "tri_state"))
    )
    (net (code "81") (name "Net-(D1G-C)") (class "Default")
      (node (ref "D1") (pin "14") (pinfunction "C_14") (pintype "passive"))
      (node (ref "RN2") (pin "3") (pinfunction "3_3") (pintype "passive"))
    )
    (net (code "82") (name "Net-(D1H-A)") (class "Default")
      (node (ref "D1") (pin "8") (pinfunction "A_8") (pintype "passive"))
      (node (ref "IC3") (pin "5") (pinfunction "QF_5") (pintype "tri_state"))
    )
    (net (code "83") (name "Net-(D1H-C)") (class "Default")
      (node (ref "D1") (pin "13") (pinfunction "C_13") (pintype "passive"))
      (node (ref "RN2") (pin "4") (pinfunction "4_4") (pintype "passive"))
    )
    (net (code "84") (name "Net-(D1I-A)") (class "Default")
      (node (ref "D1") (pin "9") (pinfunction "A_9") (pintype "passive"))
      (node (ref "IC3") (pin "6") (pinfunction "QG_6") (pintype "tri_state"))
    )
    (net (code "85") (name "Net-(D1I-C)") (class "Default")
      (node (ref "D1") (pin "12") (pinfunction "C_12") (pintype "passive"))
      (node (ref "RN2") (pin "5") (pinfunction "5_5") (pintype "passive"))
    )
    (net (code "86") (name "Net-(D1J-A)") (class "Default")
      (node (ref "D1") (pin "10") (pinfunction "A_10") (pintype "passive"))
      (node (ref "IC3") (pin "7") (pinfunction "QH_7") (pintype "tri_state"))
    )
    (net (code "87") (name "Net-(D1J-C)") (class "Default")
      (node (ref "D1") (pin "11") (pinfunction "C_11") (pintype "passive"))
      (node (ref "RN2") (pin "6") (pinfunction "6_6") (pintype "passive"))
    )
    (net (code "88") (name "Net-(D2-RS)") (class "Default")
      (node (ref "D2") (pin "8") (pinfunction "RS_8") (pintype "input"))
      (node (ref "R10") (pin "1") (pinfunction "1_1") (pintype "passive"))
    )
    (net (code "89") (name "Net-(IC1-SER)") (class "Default")
      (node (ref "IC1") (pin "14") (pinfunction "SER_14") (pintype "input"))
      (node (ref "IC2") (pin "9") (pinfunction "QH*_9") (pintype "tri_state"))
    )
    (net (code "90") (name "Net-(IC2-SER)") (class "Default")
      (node (ref "IC2") (pin "14") (pinfunction "SER_14") (pintype "input"))
      (node (ref "IC3") (pin "9") (pinfunction "QH*_9") (pintype "tri_state"))
    )
    (net (code "91") (name "Net-(IC4-QH)") (class "Default")
      (node (ref "IC4") (pin "9") (pinfunction "QH_9") (pintype "tri_state"))
      (node (ref "IC5") (pin "10") (pinfunction "SER_10") (pintype "input"))
      (node (ref "R1") (pin "1") (pinfunction "1_1") (pintype "passive"))
    )
    (net (code "92") (name "Net-(IC4-SER)") (class "Default")
      (node (ref "IC4") (pin "10") (pinfunction "SER_10") (pintype "input"))
      (node (ref "R38") (pin "1") (pinfunction "1_1") (pintype "passive"))
    )
    (net (code "93") (name "Net-(LED-PadA)") (class "Default")
      (node (ref "LED") (pin "A") (pinfunction "A_A") (pintype "passive"))
      (node (ref "R2") (pin "1") (pinfunction "1_1") (pintype "passive"))
    )
    (net (code "94") (name "Net-(PWR-PadA)") (class "Default")
      (node (ref "PWR") (pin "A") (pinfunction "A_A") (pintype "passive"))
      (node (ref "R17") (pin "1") (pinfunction "1_1") (pintype "passive"))
    )
    (net (code "95") (name "Net-(R3-Pad1)") (class "Default")
      (node (ref "R3") (pin "1") (pinfunction "1_1") (pintype "passive"))
      (node (ref "TERM") (pin "4") (pinfunction "4_4") (pintype "passive"))
    )
    (net (code "96") (name "Net-(R7-Pad2)") (class "Default")
      (node (ref "R7") (pin "2") (pinfunction "2_2") (pintype "passive"))
      (node (ref "TERM") (pin "2") (pinfunction "2_2") (pintype "passive"))
    )
    (net (code "97") (name "Net-(ROT1-CH_A)") (class "Default")
      (node (ref "R39") (pin "2") (pinfunction "2_2") (pintype "passive"))
      (node (ref "R41") (pin "2") (pinfunction "2_2") (pintype "passive"))
      (node (ref "ROT1") (pin "A") (pinfunction "CH_A_A") (pintype "output"))
    )
    (net (code "98") (name "Net-(ROT1-CH_B)") (class "Default")
      (node (ref "R40") (pin "2") (pinfunction "2_2") (pintype "passive"))
      (node (ref "R42") (pin "2") (pinfunction "2_2") (pintype "passive"))
      (node (ref "ROT1") (pin "B") (pinfunction "CH_B_B") (pintype "output"))
    )
    (net (code "99") (name "Net-(ROT2-CH_A)") (class "Default")
      (node (ref "R43") (pin "2") (pinfunction "2_2") (pintype "passive"))
      (node (ref "R45") (pin "2") (pinfunction "2_2") (pintype "passive"))
      (node (ref "ROT2") (pin "A") (pinfunction "CH_A_A") (pintype "output"))
    )
    (net (code "100") (name "Net-(ROT2-CH_B)") (class "Default")
      (node (ref "R44") (pin "2") (pinfunction "2_2") (pintype "passive"))
      (node (ref "R46") (pin "2") (pinfunction "2_2") (pintype "passive"))
      (node (ref "ROT2") (pin "B") (pinfunction "CH_B_B") (pintype "output"))
    )
    (net (code "101") (name "PB2") (class "Default")
      (node (ref "CPU1") (pin "28") (pinfunction "PB2-BOOT1_28") (pintype "bidirectional"))
      (node (ref "USR") (pin "B") (pinfunction "S_B") (pintype "passive"))
      (node (ref "USR") (pin "B'") (pinfunction "S1_B'") (pintype "passive"))
    )
    (net (code "102") (name "POT1") (class "Default")
      (node (ref "CPU1") (pin "15") (pinfunction "PA1_15") (pintype "bidirectional"))
      (node (ref "POT1") (pin "CENTER") (pinfunction "WIPER_CENTER") (pintype "passive"))
    )
    (net (code "103") (name "POT2") (class "Default")
      (node (ref "CPU1") (pin "23") (pinfunction "PA7/SPI1_MOSI_23") (pintype "bidirectional"))
      (node (ref "POT2") (pin "CENTER") (pinfunction "WIPER_CENTER") (pintype "passive"))
    )
    (net (code "104") (name "POT3") (class "Default")
      (node (ref "CPU1") (pin "16") (pinfunction "PA2/UART2_TX_16") (pintype "bidirectional"))
      (node (ref "POT3") (pin "CENTER") (pinfunction "WIPER_CENTER") (pintype "passive"))
    )
    (net (code "105") (name "POT4") (class "Default")
      (node (ref "CPU1") (pin "22") (pinfunction "PA6/SPI1_MISO_22") (pintype "bidirectional"))
      (node (ref "POT4") (pin "CENTER") (pinfunction "WIPER_CENTER") (pintype "passive"))
    )
    (net (code "106") (name "POT5") (class "Default")
      (node (ref "CPU1") (pin "17") (pinfunction "PA3/UART2_RX_17") (pintype "bidirectional"))
      (node (ref "POT5") (pin "CENTER") (pinfunction "WIPER_CENTER") (pintype "passive"))
    )
    (net (code "107") (name "POT6") (class "Default")
      (node (ref "CPU1") (pin "20") (pinfunction "PA4/SPI1_NSS_20") (pintype "bidirectional"))
      (node (ref "POT6") (pin "CENTER") (pinfunction "WIPER_CENTER") (pintype "passive"))
    )
    (net (code "108") (name "POT7") (class "Default")
      (node (ref "CPU1") (pin "21") (pinfunction "PA5/SPI1_SCK_21") (pintype "bidirectional"))
      (node (ref "POT7") (pin "CENTER") (pinfunction "WIPER_CENTER") (pintype "passive"))
    )
    (net (code "109") (name "SPI2_CLK") (class "Default")
      (node (ref "CPU1") (pin "34") (pinfunction "PB13/I2S2_CK_34") (pintype "bidirectional"))
      (node (ref "IC1") (pin "11") (pinfunction "SCK_11") (pintype "input"))
      (node (ref "IC2") (pin "11") (pinfunction "SCK_11") (pintype "input"))
      (node (ref "IC3") (pin "11") (pinfunction "SCK_11") (pintype "input"))
      (node (ref "IC4") (pin "2") (pinfunction "CLK_2") (pintype "input"))
      (node (ref "IC5") (pin "2") (pinfunction "CLK_2") (pintype "input"))
    )
    (net (code "110") (name "SPI2_MISO") (class "Default")
      (node (ref "CPU1") (pin "35") (pinfunction "PB14/I2S2_XD_35") (pintype "bidirectional"))
      (node (ref "IC5") (pin "9") (pinfunction "QH_9") (pintype "tri_state"))
    )
    (net (code "111") (name "SPI2_MOSI") (class "Default")
      (node (ref "CPU1") (pin "36") (pinfunction "PB15/I2S2_SD_36") (pintype "bidirectional"))
      (node (ref "IC3") (pin "14") (pinfunction "SER_14") (pintype "input"))
    )
    (net (code "112") (name "SPI2_RC1") (class "Default")
      (node (ref "CPU1") (pin "11") (pinfunction "PC3_11") (pintype "bidirectional"))
      (node (ref "IC1") (pin "12") (pinfunction "RCK_12") (pintype "input"))
      (node (ref "IC2") (pin "12") (pinfunction "RCK_12") (pintype "input"))
      (node (ref "IC3") (pin "12") (pinfunction "RCK_12") (pintype "input"))
    )
    (net (code "113") (name "SPI2_RC2") (class "Default")
      (node (ref "CPU1") (pin "10") (pinfunction "PC2_10") (pintype "bidirectional"))
      (node (ref "IC4") (pin "1") (pinfunction "SH/~{LD}_1") (pintype "input"))
      (node (ref "IC5") (pin "1") (pinfunction "SH/~{LD}_1") (pintype "input"))
    )
    (net (code "114") (name "SWCK") (class "Default")
      (node (ref "CPU1") (pin "49") (pinfunction "PA14/JTCK_49") (pintype "bidirectional"))
      (node (ref "TC1") (pin "4") (pinfunction "4_4") (pintype "passive"))
    )
    (net (code "115") (name "SWDIO") (class "Default")
      (node (ref "CPU1") (pin "46") (pinfunction "PA13/JTMS_46") (pintype "bidirectional"))
      (node (ref "TC1") (pin "2") (pinfunction "2_2") (pintype "passive"))
    )
    (net (code "116") (name "UART_RX") (class "Default")
      (node (ref "CPU1") (pin "52") (pinfunction "PC11/SDIO_D3_52") (pintype "bidirectional"))
      (node (ref "TC1") (pin "8") (pinfunction "8_8") (pintype "passive"))
    )
    (net (code "117") (name "UART_TX") (class "Default")
      (node (ref "CPU1") (pin "51") (pinfunction "PC10/SDIO_D2_51") (pintype "bidirectional"))
      (node (ref "TC1") (pin "6") (pinfunction "6_6") (pintype "passive"))
    )
    (net (code "118") (name "unconnected-(CPU1-PA8-Pad41)") (class "Default")
      (node (ref "CPU1") (pin "41") (pinfunction "PA8_41") (pintype "bidirectional"))
    )
    (net (code "119") (name "unconnected-(CPU1-PA9{slash}UART1_TX-Pad42)") (class "Default")
      (node (ref "CPU1") (pin "42") (pinfunction "PA9/UART1_TX_42") (pintype "bidirectional"))
    )
    (net (code "120") (name "unconnected-(CPU1-PA10{slash}UART1_RX-Pad43)") (class "Default")
      (node (ref "CPU1") (pin "43") (pinfunction "PA10/UART1_RX_43") (pintype "bidirectional"))
    )
    (net (code "121") (name "unconnected-(CPU1-PA11-Pad44)") (class "Default")
      (node (ref "CPU1") (pin "44") (pinfunction "PA11_44") (pintype "bidirectional"))
    )
    (net (code "122") (name "unconnected-(CPU1-PA12-Pad45)") (class "Default")
      (node (ref "CPU1") (pin "45") (pinfunction "PA12_45") (pintype "bidirectional"))
    )
    (net (code "123") (name "unconnected-(CPU1-PA15{slash}JTDI-Pad50)") (class "Default")
      (node (ref "CPU1") (pin "50") (pinfunction "PA15/JTDI_50") (pintype "bidirectional"))
    )
    (net (code "124") (name "unconnected-(CPU1-PB0-Pad26)") (class "Default")
      (node (ref "CPU1") (pin "26") (pinfunction "PB0_26") (pintype "bidirectional"))
    )
    (net (code "125") (name "unconnected-(CPU1-PB1-Pad27)") (class "Default")
      (node (ref "CPU1") (pin "27") (pinfunction "PB1_27") (pintype "bidirectional"))
    )
    (net (code "126") (name "unconnected-(CPU1-PB10-Pad29)") (class "Default")
      (node (ref "CPU1") (pin "29") (pinfunction "PB10_29") (pintype "bidirectional"))
    )
    (net (code "127") (name "unconnected-(CPU1-PB11-Pad30)") (class "Default")
      (node (ref "CPU1") (pin "30") (pinfunction "PB11_30") (pintype "bidirectional"))
    )
    (net (code "128") (name "unconnected-(CPU1-PB12{slash}I2S2_WS-Pad33)") (class "Default")
      (node (ref "CPU1") (pin "33") (pinfunction "PB12/I2S2_WS_33") (pintype "bidirectional"))
    )
    (net (code "129") (name "unconnected-(CPU1-PC0-Pad8)") (class "Default")
      (node (ref "CPU1") (pin "8") (pinfunction "PC0_8") (pintype "bidirectional"))
    )
    (net (code "130") (name "unconnected-(CPU1-PC1-Pad9)") (class "Default")
      (node (ref "CPU1") (pin "9") (pinfunction "PC1_9") (pintype "bidirectional"))
    )
    (net (code "131") (name "unconnected-(CPU1-PC4-Pad24)") (class "Default")
      (node (ref "CPU1") (pin "24") (pinfunction "PC4_24") (pintype "bidirectional"))
    )
    (net (code "132") (name "unconnected-(CPU1-PC6{slash}I2S2_MCK-Pad37)") (class "Default")
      (node (ref "CPU1") (pin "37") (pinfunction "PC6/I2S2_MCK_37") (pintype "bidirectional"))
    )
    (net (code "133") (name "unconnected-(CPU1-PC7-Pad38)") (class "Default")
      (node (ref "CPU1") (pin "38") (pinfunction "PC7_38") (pintype "bidirectional"))
    )
    (net (code "134") (name "unconnected-(CPU1-PC8{slash}SDIO_D0-Pad39)") (class "Default")
      (node (ref "CPU1") (pin "39") (pinfunction "PC8/SDIO_D0_39") (pintype "bidirectional"))
    )
    (net (code "135") (name "unconnected-(CPU1-PC9{slash}SDIO_D1-Pad40)") (class "Default")
      (node (ref "CPU1") (pin "40") (pinfunction "PC9/SDIO_D1_40") (pintype "bidirectional"))
    )
    (net (code "136") (name "unconnected-(CPU1-PC12{slash}SDIO_CLK-Pad53)") (class "Default")
      (node (ref "CPU1") (pin "53") (pinfunction "PC12/SDIO_CLK_53") (pintype "bidirectional"))
    )
    (net (code "137") (name "unconnected-(CPU1-PC13-Pad2)") (class "Default")
      (node (ref "CPU1") (pin "2") (pinfunction "PC13_2") (pintype "bidirectional"))
    )
    (net (code "138") (name "unconnected-(CPU1-PC14-Pad3)") (class "Default")
      (node (ref "CPU1") (pin "3") (pinfunction "PC14_3") (pintype "bidirectional"))
    )
    (net (code "139") (name "unconnected-(CPU1-PC15-Pad4)") (class "Default")
      (node (ref "CPU1") (pin "4") (pinfunction "PC15_4") (pintype "bidirectional"))
    )
    (net (code "140") (name "unconnected-(IC1-QH*-Pad9)") (class "Default")
      (node (ref "IC1") (pin "9") (pinfunction "QH*_9") (pintype "tri_state"))
    )
    (net (code "141") (name "unconnected-(IC4-~{QH}-Pad7)") (class "Default")
      (node (ref "IC4") (pin "7") (pinfunction "~{QH}_7") (pintype "input"))
    )
    (net (code "142") (name "unconnected-(IC5-~{QH}-Pad7)") (class "Default")
      (node (ref "IC5") (pin "7") (pinfunction "~{QH}_7") (pintype "input"))
    )
    (net (code "143") (name "unconnected-(POT1-CHASSIS-Pad4)") (class "Default")
      (node (ref "POT1") (pin "4") (pinfunction "CHASSIS_4") (pintype "passive"))
    )
    (net (code "144") (name "unconnected-(POT2-CHASSIS-Pad4)") (class "Default")
      (node (ref "POT2") (pin "4") (pinfunction "CHASSIS_4") (pintype "passive"))
    )
    (net (code "145") (name "unconnected-(POT3-CHASSIS-Pad4)") (class "Default")
      (node (ref "POT3") (pin "4") (pinfunction "CHASSIS_4") (pintype "passive"))
    )
    (net (code "146") (name "unconnected-(POT4-CHASSIS-Pad4)") (class "Default")
      (node (ref "POT4") (pin "4") (pinfunction "CHASSIS_4") (pintype "passive"))
    )
    (net (code "147") (name "unconnected-(POT5-CHASSIS-Pad4)") (class "Default")
      (node (ref "POT5") (pin "4") (pinfunction "CHASSIS_4") (pintype "passive"))
    )
    (net (code "148") (name "unconnected-(POT6-CHASSIS-Pad4)") (class "Default")
      (node (ref "POT6") (pin "4") (pinfunction "CHASSIS_4") (pintype "passive"))
    )
    (net (code "149") (name "unconnected-(POT7-CHASSIS-Pad4)") (class "Default")
      (node (ref "POT7") (pin "4") (pinfunction "CHASSIS_4") (pintype "passive"))
    )
    (net (code "150") (name "unconnected-(TC1-Pad7)") (class "Default")
      (node (ref "TC1") (pin "7") (pinfunction "7_7") (pintype "passive"))
    )
  )
)
